# royersmd.net
KiCad netlist of a schematic drawn in EAGLE
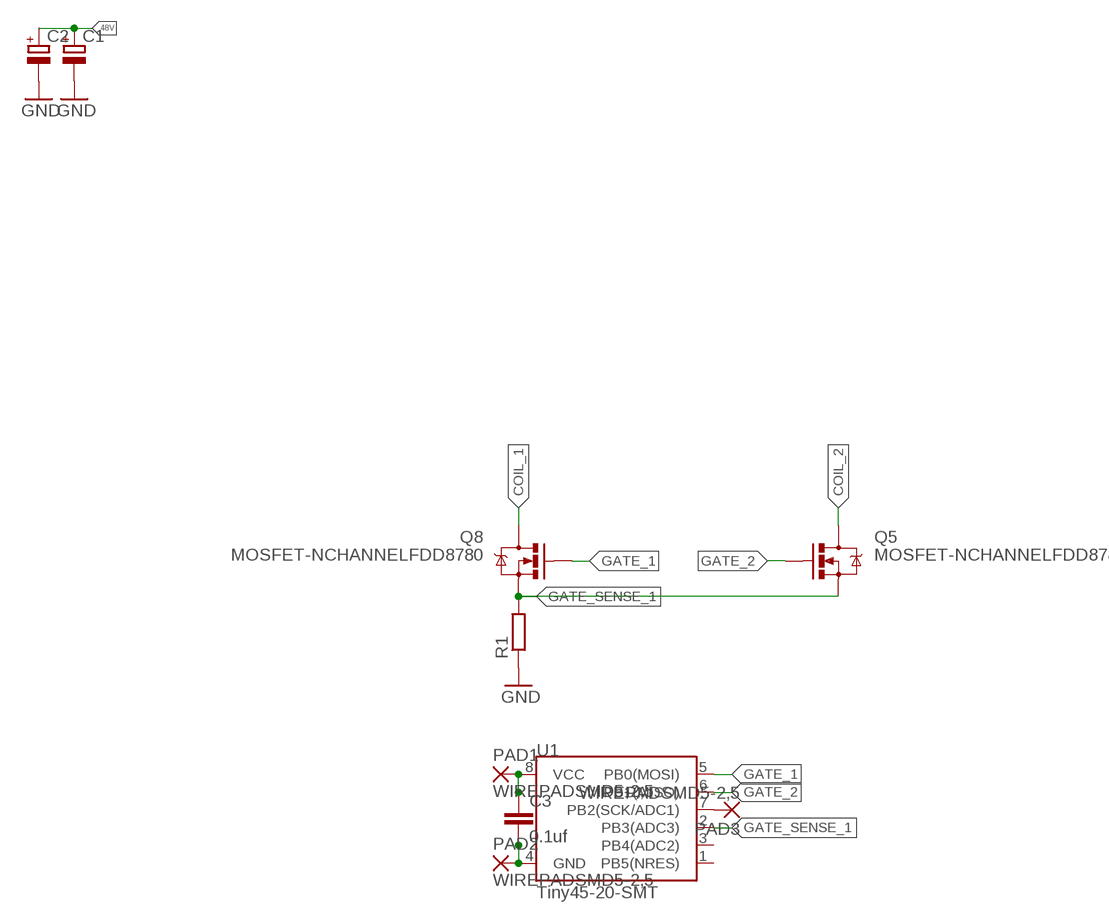
[diagram p0: schematic, sheet 1]

(export (version "E")
  (design (tool "Eeschema 10.0.6"))
  (components
    (comp (ref "C1")
      (value "CPOL-EUSANYO_9F")
      (footprint "eagle-import:SANYO-OSCON_9F")
      (libsource (lib "eagle-import") (part "CPOL-EUSANYO_9F"))
    )
    (comp (ref "C2")
      (value "CPOL-EUSANYO_9F")
      (footprint "eagle-import:SANYO-OSCON_9F")
      (libsource (lib "eagle-import") (part "CPOL-EUSANYO_9F"))
    )
    (comp (ref "C3")
      (value "0.1uf")
      (footprint "eagle-import:C0603")
      (libsource (lib "eagle-import") (part "C-EUC0603"))
    )
    (comp (ref "PAD1")
      (value "WIREPADSMD5-2,5")
      (footprint "eagle-import:5-2,5")
      (libsource (lib "eagle-import") (part "WIREPADSMD5-2,5"))
    )
    (comp (ref "PAD2")
      (value "WIREPADSMD5-2,5")
      (footprint "eagle-import:5-2,5")
      (libsource (lib "eagle-import") (part "WIREPADSMD5-2,5"))
    )
    (comp (ref "PAD3")
      (value "WIREPADSMD5-2,5")
      (footprint "eagle-import:5-2,5")
      (libsource (lib "eagle-import") (part "WIREPADSMD5-2,5"))
    )
    (comp (ref "Q5")
      (value "MOSFET-NCHANNELFDD8780")
      (footprint "eagle-import:DPAK")
      (libsource (lib "eagle-import") (part "MOSFET-NCHANNELFDD8780"))
    )
    (comp (ref "Q8")
      (value "MOSFET-NCHANNELFDD8780")
      (footprint "eagle-import:DPAK")
      (libsource (lib "eagle-import") (part "MOSFET-NCHANNELFDD8780"))
    )
    (comp (ref "R1")
      (value "R-EU_M1206")
      (footprint "eagle-import:M1206")
      (libsource (lib "eagle-import") (part "R-EU_M1206"))
    )
    (comp (ref "U1")
      (value "Tiny45-20-SMT")
      (footprint "eagle-import:SO08-EIAJ")
      (libsource (lib "eagle-import") (part "ATTINY45TINY45-20-SMT"))
    )
  )
  (nets
    (net (code "1") (name "48V") (class "Default")
      (node (ref "C1") (pin "+") (pinfunction "+_+") (pintype "passive"))
      (node (ref "C2") (pin "+") (pinfunction "+_+") (pintype "passive"))
    )
    (net (code "2") (name "COIL_1") (class "Default")
      (node (ref "Q8") (pin "4") (pinfunction "D_4") (pintype "passive"))
    )
    (net (code "3") (name "COIL_2") (class "Default")
      (node (ref "Q5") (pin "4") (pinfunction "D_4") (pintype "passive"))
    )
    (net (code "4") (name "GATE_1") (class "Default")
      (node (ref "Q8") (pin "1") (pinfunction "G_1") (pintype "passive"))
      (node (ref "U1") (pin "5") (pinfunction "PB0(MOSI)_5") (pintype "bidirectional"))
    )
    (net (code "5") (name "GATE_2") (class "Default")
      (node (ref "Q5") (pin "1") (pinfunction "G_1") (pintype "passive"))
      (node (ref "U1") (pin "6") (pinfunction "PB1(MISO)_6") (pintype "bidirectional"))
    )
    (net (code "6") (name "GATE_SENSE_1") (class "Default")
      (node (ref "Q5") (pin "3") (pinfunction "S_3") (pintype "passive"))
      (node (ref "Q8") (pin "3") (pinfunction "S_3") (pintype "passive"))
      (node (ref "R1") (pin "2") (pinfunction "2_2") (pintype "passive"))
      (node (ref "U1") (pin "2") (pinfunction "PB3(ADC3)_2") (pintype "bidirectional"))
    )
    (net (code "7") (name "GND") (class "Default")
      (node (ref "C1") (pin "-") (pinfunction "-_-") (pintype "passive"))
      (node (ref "C2") (pin "-") (pinfunction "-_-") (pintype "passive"))
      (node (ref "R1") (pin "1") (pinfunction "1_1") (pintype "passive"))
    )
    (net (code "8") (name "Net-(PAD1-P)") (class "Default")
      (node (ref "C3") (pin "1") (pinfunction "1_1") (pintype "passive"))
      (node (ref "PAD1") (pin "1") (pinfunction "P_1") (pintype "passive"))
      (node (ref "U1") (pin "8") (pinfunction "VCC_8") (pintype "bidirectional"))
    )
    (net (code "9") (name "Net-(PAD2-P)") (class "Default")
      (node (ref "C3") (pin "2") (pinfunction "2_2") (pintype "passive"))
      (node (ref "PAD2") (pin "1") (pinfunction "P_1") (pintype "passive"))
      (node (ref "U1") (pin "4") (pinfunction "GND_4") (pintype "bidirectional"))
    )
    (net (code "10") (name "Net-(PAD3-P)") (class "Default")
      (node (ref "PAD3") (pin "1") (pinfunction "P_1") (pintype "passive"))
      (node (ref "U1") (pin "7") (pinfunction "PB2(SCK/ADC1)_7") (pintype "bidirectional"))
    )
    (net (code "11") (name "unconnected-(U1-PB4(ADC2)-Pad3)") (class "Default")
      (node (ref "U1") (pin "3") (pinfunction "PB4(ADC2)_3") (pintype "bidirectional"))
    )
    (net (code "12") (name "unconnected-(U1-PB5(NRES)-Pad1)") (class "Default")
      (node (ref "U1") (pin "1") (pinfunction "PB5(NRES)_1") (pintype "bidirectional"))
    )
  )
)
